# bop_it_sch.net
KiCad netlist of a schematic drawn in Altium Designer
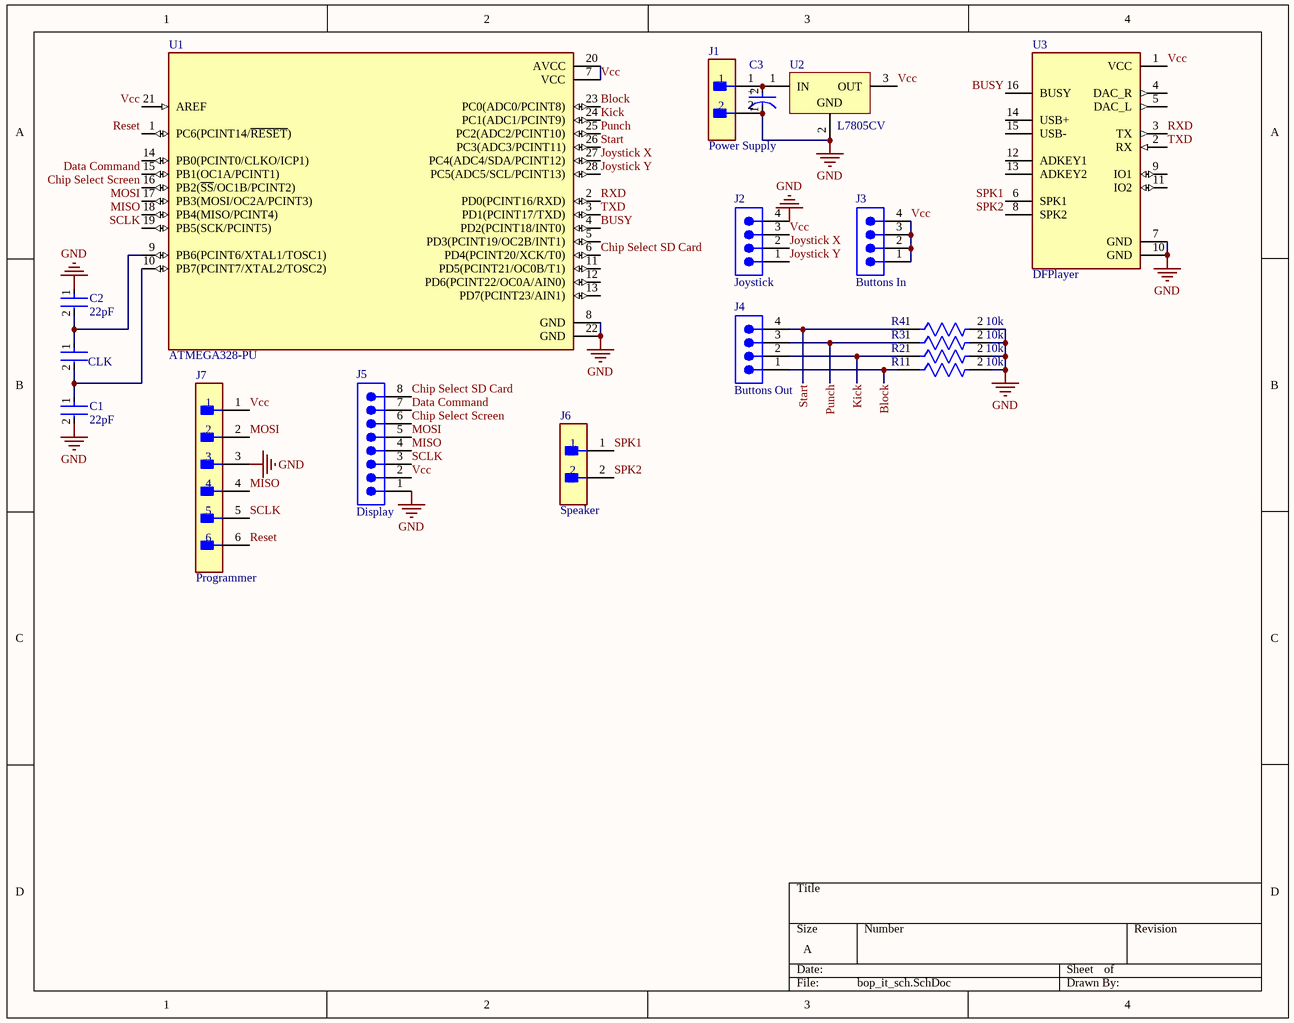
[diagram p0: bop_it_sch.SchDoc]

(export (version "E")
  (design (tool "Eeschema 10.0.6"))
  (components
    (comp (ref "C1")
      (value "22pF")
      (footprint "FP-RDE0M1-MFG")
      (description "Ceramic Capacitor 10nF ±10% 50V X7R Radial")
      (fields (field (name "TOLERANCE") "10%"))
      (libsource (lib "Altium Content Vault") (part "b4654b650e69147ec39a6b967a45e02"))
    )
    (comp (ref "C2")
      (value "22pF")
      (footprint "FP-RDE0M1-MFG")
      (description "Ceramic Capacitor 10nF ±10% 50V X7R Radial")
      (fields (field (name "TOLERANCE") "10%"))
      (libsource (lib "Altium Content Vault") (part "b4654b650e69147ec39a6b967a45e02"))
    )
    (comp (ref "C3")
      (value "~")
      (footprint "FP-RAD-TH-D_5_0_5-L_11_1-MFG")
      (description "Aluminum Electrolytic Capacitors (Radial Lead Type) 1uF ±20% 50V")
      (fields (field (name "TOLERANCE") "20%"))
      (libsource (lib "Altium Content Vault") (part "a00bbbee19879c290e62620ae7e47b1"))
    )
    (comp (ref "CLK")
      (value "~")
      (footprint "FP-RDE0M1-MFG")
      (description "Ceramic Capacitor 10nF ±10% 50V X7R Radial")
      (fields (field (name "TOLERANCE") "10%"))
      (libsource (lib "Altium Content Vault") (part "b4654b650e69147ec39a6b967a45e02"))
    )
    (comp (ref "J1")
      (value "Power Supply")
      (footprint "FP-M20-9990246-MFG")
      (description "Connector Header Through Hole 2 position 0.100\" (2.54mm)")
      (fields (field (name "OCTOPART") "https://octopart.com/m20-9990246-harwin-2590635"))
      (libsource (lib "Altium Content Vault") (part "3bc925449376181038e59eaffc5286c"))
    )
    (comp (ref "J2")
      (value "Joystick")
      (footprint "61300411121")
      (libsource (lib "Altium Content Vault") (part "Header_Male_1R_04P"))
    )
    (comp (ref "J3")
      (value "Buttons In")
      (footprint "61300411121")
      (libsource (lib "Altium Content Vault") (part "Header_Male_1R_04P"))
    )
    (comp (ref "J4")
      (value "Buttons Out")
      (footprint "61300411121")
      (libsource (lib "Altium Content Vault") (part "Header_Male_1R_04P"))
    )
    (comp (ref "J5")
      (value "Display")
      (footprint "61300811121")
      (libsource (lib "Altium Content Vault") (part "Header_Male_1R_08P"))
    )
    (comp (ref "J6")
      (value "Speaker")
      (footprint "FP-M20-9990246-MFG")
      (description "Connector Header Through Hole 2 position 0.100\" (2.54mm)")
      (fields (field (name "OCTOPART") "https://octopart.com/m20-9990246-harwin-2590635"))
      (libsource (lib "Altium Content Vault") (part "3bc925449376181038e59eaffc5286c"))
    )
    (comp (ref "J7")
      (value "Programmer")
      (footprint "FP-22-28-4060-MFG")
      (description "CONN HEADER VERT 6POS 2.54MM")
      (libsource (lib "Altium Content Vault") (part "f2cb566baf1c37ab5a3b8e90bbeafd6"))
    )
    (comp (ref "R1")
      (value "10k")
      (footprint "FP-MBB0207-MFG")
      (description "RES 10K OHM 0.6W 1% AXIAL")
      (fields (field (name "TOLERANCE") "1%"))
      (libsource (lib "Altium Content Vault") (part "1029c3af85768c4190bb7ad29bc67b5"))
    )
    (comp (ref "R2")
      (value "10k")
      (footprint "FP-MBB0207-MFG")
      (description "RES 10K OHM 0.6W 1% AXIAL")
      (fields (field (name "TOLERANCE") "1%"))
      (libsource (lib "Altium Content Vault") (part "1029c3af85768c4190bb7ad29bc67b5"))
    )
    (comp (ref "R3")
      (value "10k")
      (footprint "FP-MBB0207-MFG")
      (description "RES 10K OHM 0.6W 1% AXIAL")
      (fields (field (name "TOLERANCE") "1%"))
      (libsource (lib "Altium Content Vault") (part "1029c3af85768c4190bb7ad29bc67b5"))
    )
    (comp (ref "R4")
      (value "10k")
      (footprint "FP-MBB0207-MFG")
      (description "RES 10K OHM 0.6W 1% AXIAL")
      (fields (field (name "TOLERANCE") "1%"))
      (libsource (lib "Altium Content Vault") (part "1029c3af85768c4190bb7ad29bc67b5"))
    )
    (comp (ref "U1")
      (value "ATMEGA328-PU")
      (footprint "DIP787W46P254L3467H508Q28")
      (description "AVR AVRÂ® ATmega Microcontroller IC 8-Bit 20MHz 32KB (16K x 16) FLASH 28-PDIP")
      (fields (field (name "MF") "Microchip"))
      (libsource (lib "ATMEGA328-PU") (part "ATMEGA328-PU"))
    )
    (comp (ref "U2")
      (value "L7805CV")
      (footprint "TO220FP")
      (description "Positive Voltage Regulator, 5V, 3-Pin TO-220FP")
      (libsource (lib "Altium Content Vault") (part "PM-REG-L4940-SIL3"))
    )
    (comp (ref "U3")
      (value "DFPlayer")
      (footprint "MODULE_DFR0299")
      (description "- MP3 Player Audio Arduino Platform Evaluation Expansion Board")
      (fields (field (name "MF") "DFRobot") (field (name "MP") "DFR0299"))
      (libsource (lib "DFR0299") (part "DFR0299"))
    )
  )
  (nets
    (net (code "1") (name "/BUSY") (class "Default")
      (node (ref "U1") (pin "4") (pinfunction "PD2(PCINT18/INT0)_4") (pintype "bidirectional"))
      (node (ref "U3") (pin "16") (pinfunction "BUSY_16") (pintype "passive"))
    )
    (net (code "2") (name "/Block") (class "Default")
      (node (ref "J4") (pin "1") (pinfunction "1_1") (pintype "passive"))
      (node (ref "R1") (pin "1") (pinfunction "1_1") (pintype "passive"))
      (node (ref "U1") (pin "23") (pinfunction "PC0(ADC0/PCINT8)_23") (pintype "bidirectional"))
    )
    (net (code "3") (name "/Chip Select SD Card") (class "Default")
      (node (ref "J5") (pin "8") (pinfunction "8_8") (pintype "passive"))
      (node (ref "U1") (pin "6") (pinfunction "PD4(PCINT20/XCK/T0)_6") (pintype "bidirectional"))
    )
    (net (code "4") (name "/Chip Select Screen") (class "Default")
      (node (ref "J5") (pin "6") (pinfunction "6_6") (pintype "passive"))
      (node (ref "U1") (pin "16") (pinfunction "PB2(~{SS}/OC1B/PCINT2)_16") (pintype "bidirectional"))
    )
    (net (code "5") (name "/Data Command") (class "Default")
      (node (ref "J5") (pin "7") (pinfunction "7_7") (pintype "passive"))
      (node (ref "U1") (pin "15") (pinfunction "PB1(OC1A/PCINT1)_15") (pintype "bidirectional"))
    )
    (net (code "6") (name "/Joystick X") (class "Default")
      (node (ref "J2") (pin "2") (pinfunction "2_2") (pintype "passive"))
      (node (ref "U1") (pin "27") (pinfunction "PC4(ADC4/SDA/PCINT12)_27") (pintype "bidirectional"))
    )
    (net (code "7") (name "/Joystick Y") (class "Default")
      (node (ref "J2") (pin "1") (pinfunction "1_1") (pintype "passive"))
      (node (ref "U1") (pin "28") (pinfunction "PC5(ADC5/SCL/PCINT13)_28") (pintype "bidirectional"))
    )
    (net (code "8") (name "/Kick") (class "Default")
      (node (ref "J4") (pin "2") (pinfunction "2_2") (pintype "passive"))
      (node (ref "R2") (pin "1") (pinfunction "1_1") (pintype "passive"))
      (node (ref "U1") (pin "24") (pinfunction "PC1(ADC1/PCINT9)_24") (pintype "bidirectional"))
    )
    (net (code "9") (name "/MISO") (class "Default")
      (node (ref "J5") (pin "4") (pinfunction "4_4") (pintype "passive"))
      (node (ref "J7") (pin "4") (pinfunction "4_4") (pintype "passive"))
      (node (ref "U1") (pin "18") (pinfunction "PB4(MISO/PCINT4)_18") (pintype "bidirectional"))
    )
    (net (code "10") (name "/MOSI") (class "Default")
      (node (ref "J5") (pin "5") (pinfunction "5_5") (pintype "passive"))
      (node (ref "J7") (pin "2") (pinfunction "2_2") (pintype "passive"))
      (node (ref "U1") (pin "17") (pinfunction "PB3(MOSI/OC2A/PCINT3)_17") (pintype "bidirectional"))
    )
    (net (code "11") (name "/Punch") (class "Default")
      (node (ref "J4") (pin "3") (pinfunction "3_3") (pintype "passive"))
      (node (ref "R3") (pin "1") (pinfunction "1_1") (pintype "passive"))
      (node (ref "U1") (pin "25") (pinfunction "PC2(ADC2/PCINT10)_25") (pintype "bidirectional"))
    )
    (net (code "12") (name "/RXD") (class "Default")
      (node (ref "U1") (pin "2") (pinfunction "PD0(PCINT16/RXD)_2") (pintype "bidirectional"))
      (node (ref "U3") (pin "3") (pinfunction "TX_3") (pintype "output"))
    )
    (net (code "13") (name "/Reset") (class "Default")
      (node (ref "J7") (pin "6") (pinfunction "6_6") (pintype "passive"))
      (node (ref "U1") (pin "1") (pinfunction "PC6(PCINT14/~{RESET})_1") (pintype "bidirectional"))
    )
    (net (code "14") (name "/SCLK") (class "Default")
      (node (ref "J5") (pin "3") (pinfunction "3_3") (pintype "passive"))
      (node (ref "J7") (pin "5") (pinfunction "5_5") (pintype "passive"))
      (node (ref "U1") (pin "19") (pinfunction "PB5(SCK/PCINT5)_19") (pintype "bidirectional"))
    )
    (net (code "15") (name "/SPK1") (class "Default")
      (node (ref "J6") (pin "1") (pinfunction "1_1") (pintype "passive"))
      (node (ref "U3") (pin "6") (pinfunction "SPK1_6") (pintype "passive"))
    )
    (net (code "16") (name "/SPK2") (class "Default")
      (node (ref "J6") (pin "2") (pinfunction "2_2") (pintype "passive"))
      (node (ref "U3") (pin "8") (pinfunction "SPK2_8") (pintype "passive"))
    )
    (net (code "17") (name "/Start") (class "Default")
      (node (ref "J4") (pin "4") (pinfunction "4_4") (pintype "passive"))
      (node (ref "R4") (pin "1") (pinfunction "1_1") (pintype "passive"))
      (node (ref "U1") (pin "26") (pinfunction "PC3(ADC3/PCINT11)_26") (pintype "bidirectional"))
    )
    (net (code "18") (name "/TXD") (class "Default")
      (node (ref "U1") (pin "3") (pinfunction "PD1(PCINT17/TXD)_3") (pintype "bidirectional"))
      (node (ref "U3") (pin "2") (pinfunction "RX_2") (pintype "input"))
    )
    (net (code "19") (name "/Vcc") (class "Default")
      (node (ref "J2") (pin "3") (pinfunction "3_3") (pintype "passive"))
      (node (ref "J3") (pin "1") (pinfunction "1_1") (pintype "passive"))
      (node (ref "J3") (pin "2") (pinfunction "2_2") (pintype "passive"))
      (node (ref "J3") (pin "3") (pinfunction "3_3") (pintype "passive"))
      (node (ref "J3") (pin "4") (pinfunction "4_4") (pintype "passive"))
      (node (ref "J5") (pin "2") (pinfunction "2_2") (pintype "passive"))
      (node (ref "J7") (pin "1") (pinfunction "1_1") (pintype "passive"))
      (node (ref "U1") (pin "20") (pinfunction "AVCC_20") (pintype "power_in"))
      (node (ref "U1") (pin "21") (pinfunction "AREF_21") (pintype "input"))
      (node (ref "U1") (pin "7") (pinfunction "VCC_7") (pintype "power_in"))
      (node (ref "U2") (pin "3") (pinfunction "OUT_3") (pintype "power_in"))
      (node (ref "U3") (pin "1") (pinfunction "VCC_1") (pintype "power_in"))
    )
    (net (code "20") (name "GND") (class "Default")
      (node (ref "C1") (pin "2") (pinfunction "2_2") (pintype "passive"))
      (node (ref "C2") (pin "1") (pinfunction "1_1") (pintype "passive"))
      (node (ref "C3") (pin "1") (pinfunction "C_1") (pintype "passive"))
      (node (ref "J1") (pin "2") (pinfunction "2_2") (pintype "passive"))
      (node (ref "J2") (pin "4") (pinfunction "4_4") (pintype "passive"))
      (node (ref "J5") (pin "1") (pinfunction "1_1") (pintype "passive"))
      (node (ref "J7") (pin "3") (pinfunction "3_3") (pintype "passive"))
      (node (ref "R1") (pin "2") (pinfunction "2_2") (pintype "passive"))
      (node (ref "R2") (pin "2") (pinfunction "2_2") (pintype "passive"))
      (node (ref "R3") (pin "2") (pinfunction "2_2") (pintype "passive"))
      (node (ref "R4") (pin "2") (pinfunction "2_2") (pintype "passive"))
      (node (ref "U1") (pin "22") (pinfunction "GND_22") (pintype "power_in"))
      (node (ref "U1") (pin "8") (pinfunction "GND_8") (pintype "power_in"))
      (node (ref "U2") (pin "2") (pinfunction "GND_2") (pintype "power_in"))
      (node (ref "U3") (pin "10") (pinfunction "GND_10") (pintype "power_in"))
      (node (ref "U3") (pin "7") (pinfunction "GND_7") (pintype "power_in"))
    )
    (net (code "21") (name "Net-(C3-A)") (class "Default")
      (node (ref "C3") (pin "2") (pinfunction "A_2") (pintype "passive"))
      (node (ref "J1") (pin "1") (pinfunction "1_1") (pintype "passive"))
      (node (ref "U2") (pin "1") (pinfunction "IN_1") (pintype "power_in"))
    )
    (net (code "22") (name "Net-(U1-PB6(PCINT6{slash}XTAL1{slash}TOSC1))") (class "Default")
      (node (ref "C2") (pin "2") (pinfunction "2_2") (pintype "passive"))
      (node (ref "CLK") (pin "1") (pinfunction "1_1") (pintype "passive"))
      (node (ref "U1") (pin "9") (pinfunction "PB6(PCINT6/XTAL1/TOSC1)_9") (pintype "bidirectional"))
    )
    (net (code "23") (name "Net-(U1-PB7(PCINT7{slash}XTAL2{slash}TOSC2))") (class "Default")
      (node (ref "C1") (pin "1") (pinfunction "1_1") (pintype "passive"))
      (node (ref "CLK") (pin "2") (pinfunction "2_2") (pintype "passive"))
      (node (ref "U1") (pin "10") (pinfunction "PB7(PCINT7/XTAL2/TOSC2)_10") (pintype "bidirectional"))
    )
    (net (code "24") (name "unconnected-(U1-PB0(PCINT0{slash}CLKO{slash}ICP1)-Pad14)") (class "Default")
      (node (ref "U1") (pin "14") (pinfunction "PB0(PCINT0/CLKO/ICP1)_14") (pintype "bidirectional"))
    )
    (net (code "25") (name "unconnected-(U1-PD3(PCINT19{slash}OC2B{slash}INT1)-Pad5)") (class "Default")
      (node (ref "U1") (pin "5") (pinfunction "PD3(PCINT19/OC2B/INT1)_5") (pintype "bidirectional"))
    )
    (net (code "26") (name "unconnected-(U1-PD5(PCINT21{slash}OC0B{slash}T1)-Pad11)") (class "Default")
      (node (ref "U1") (pin "11") (pinfunction "PD5(PCINT21/OC0B/T1)_11") (pintype "bidirectional"))
    )
    (net (code "27") (name "unconnected-(U1-PD6(PCINT22{slash}OC0A{slash}AIN0)-Pad12)") (class "Default")
      (node (ref "U1") (pin "12") (pinfunction "PD6(PCINT22/OC0A/AIN0)_12") (pintype "bidirectional"))
    )
    (net (code "28") (name "unconnected-(U1-PD7(PCINT23{slash}AIN1)-Pad13)") (class "Default")
      (node (ref "U1") (pin "13") (pinfunction "PD7(PCINT23/AIN1)_13") (pintype "bidirectional"))
    )
    (net (code "29") (name "unconnected-(U3-ADKEY1-Pad12)") (class "Default")
      (node (ref "U3") (pin "12") (pinfunction "ADKEY1_12") (pintype "passive"))
    )
    (net (code "30") (name "unconnected-(U3-ADKEY2-Pad13)") (class "Default")
      (node (ref "U3") (pin "13") (pinfunction "ADKEY2_13") (pintype "passive"))
    )
    (net (code "31") (name "unconnected-(U3-DAC_L-Pad5)") (class "Default")
      (node (ref "U3") (pin "5") (pinfunction "DAC_L_5") (pintype "output"))
    )
    (net (code "32") (name "unconnected-(U3-DAC_R-Pad4)") (class "Default")
      (node (ref "U3") (pin "4") (pinfunction "DAC_R_4") (pintype "output"))
    )
    (net (code "33") (name "unconnected-(U3-IO1-Pad9)") (class "Default")
      (node (ref "U3") (pin "9") (pinfunction "IO1_9") (pintype "bidirectional"))
    )
    (net (code "34") (name "unconnected-(U3-IO2-Pad11)") (class "Default")
      (node (ref "U3") (pin "11") (pinfunction "IO2_11") (pintype "bidirectional"))
    )
    (net (code "35") (name "unconnected-(U3-USB+-Pad14)") (class "Default")
      (node (ref "U3") (pin "14") (pinfunction "USB+_14") (pintype "passive"))
    )
    (net (code "36") (name "unconnected-(U3-USB--Pad15)") (class "Default")
      (node (ref "U3") (pin "15") (pinfunction "USB-_15") (pintype "passive"))
    )
  )
)
